# Filter.net
KiCad netlist of a schematic drawn in Altium Designer
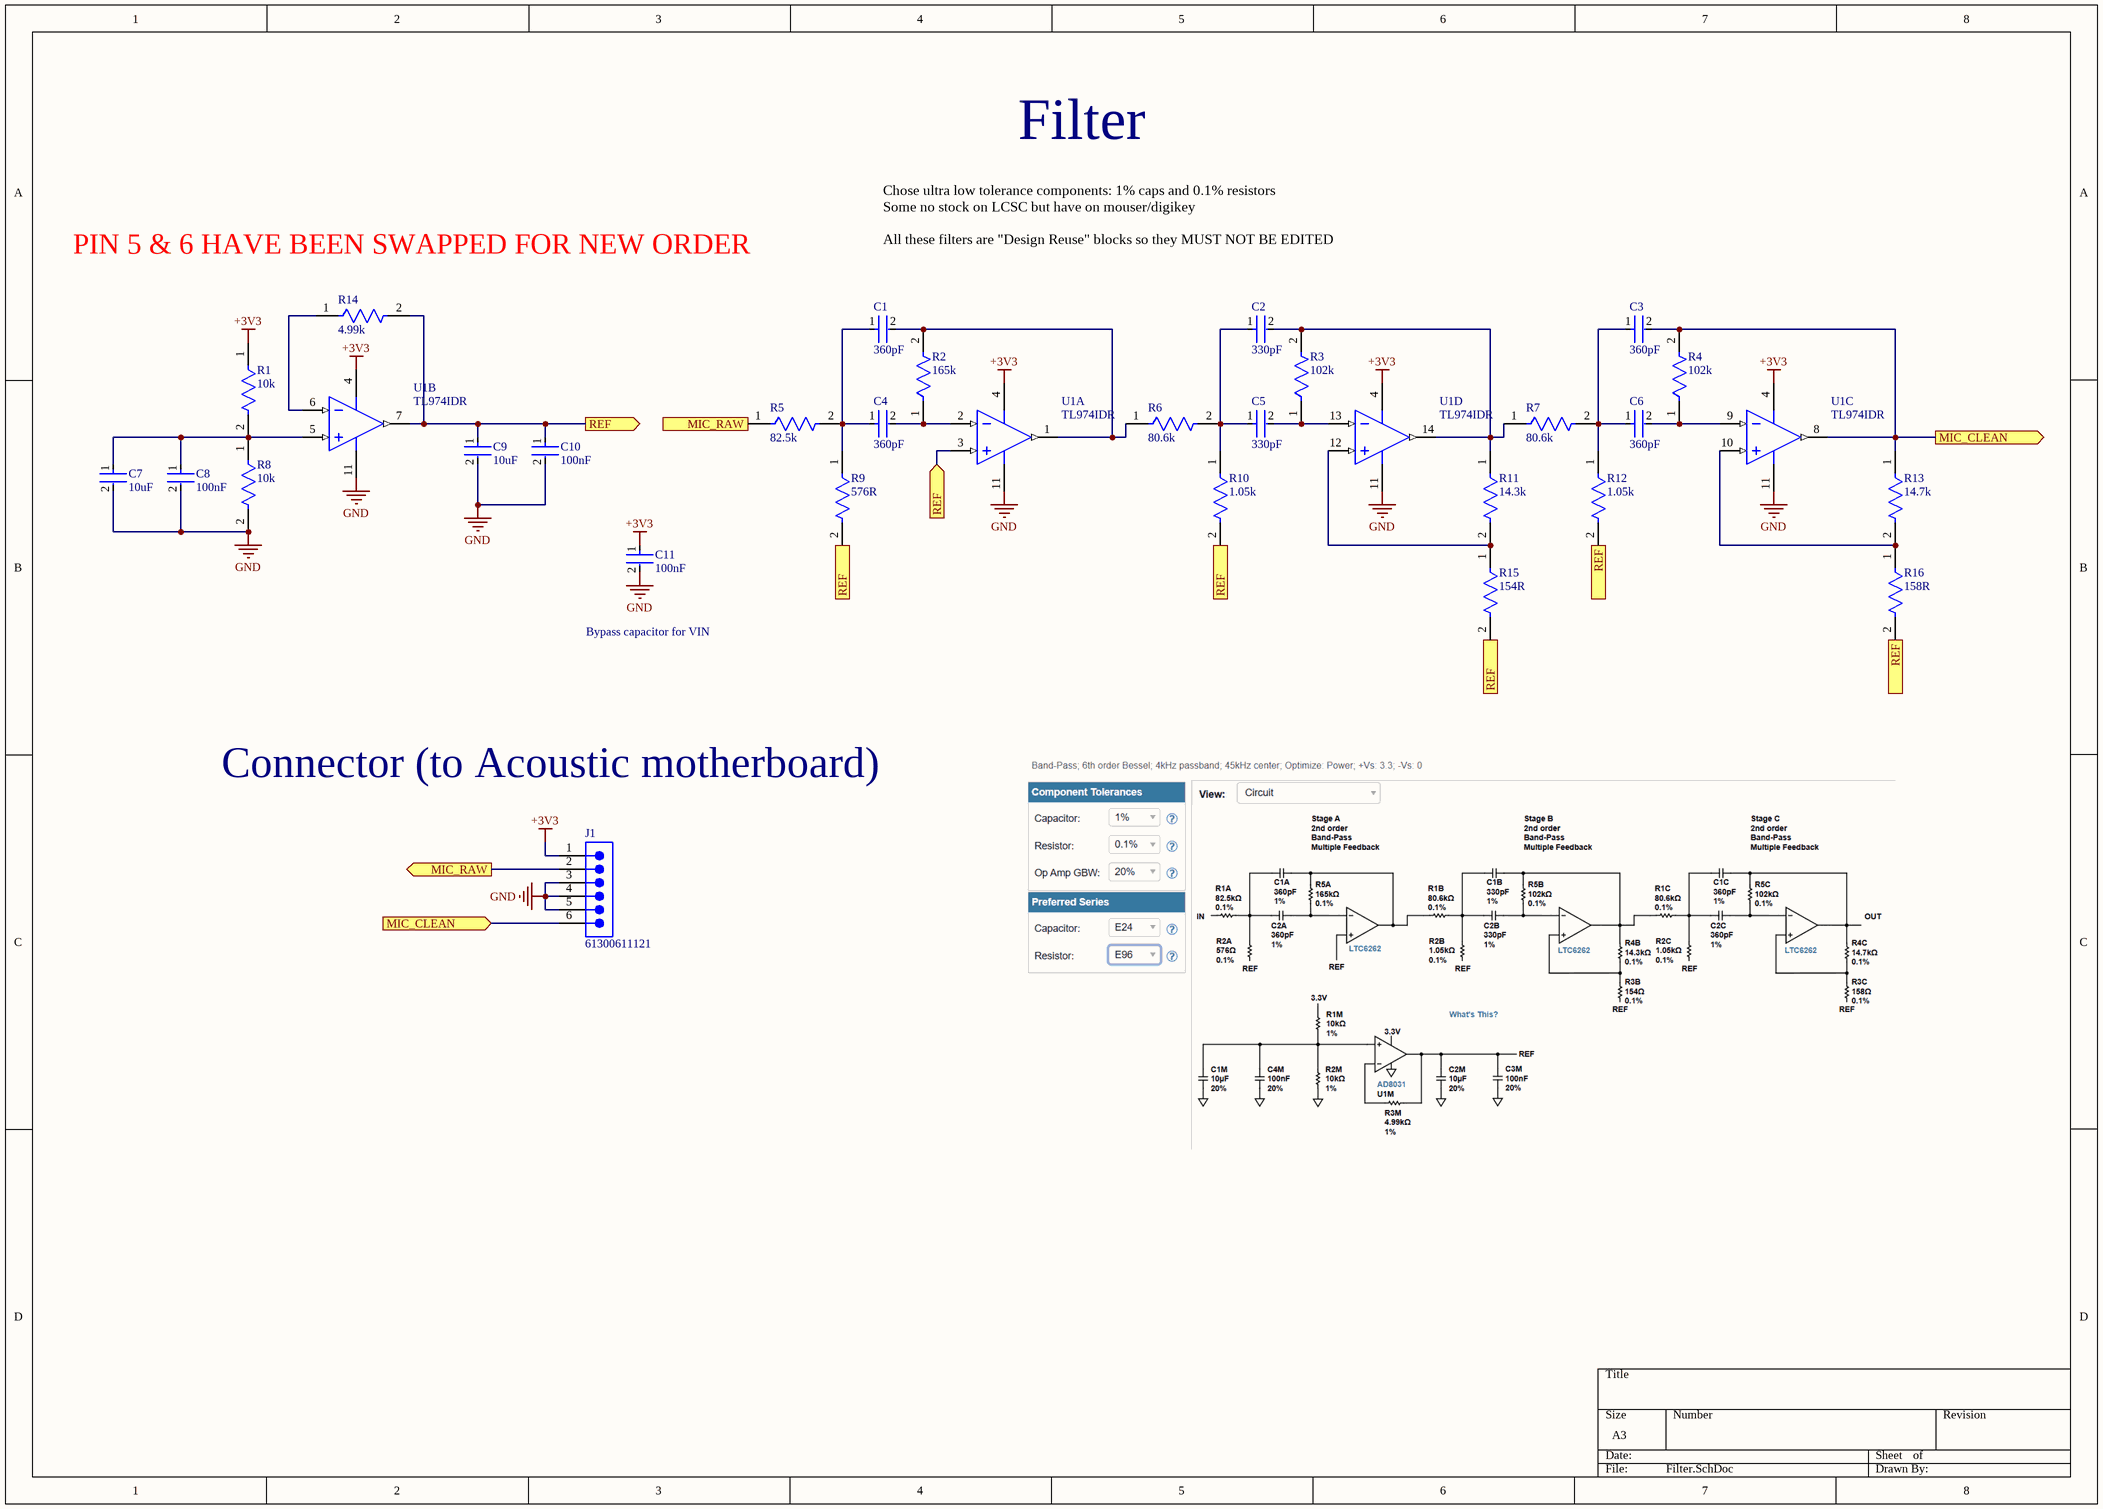
[diagram p0: Filter.SchDoc]

(export (version "E")
  (design (tool "Eeschema 10.0.6"))
  (components
    (comp (ref "C1")
      (value "360pF")
      (footprint "FP-GCM188-0_1-IPC_B")
      (libsource (lib "Hornet X Elec") (part "02cd4be3c70576c341d710602a673aa"))
    )
    (comp (ref "C2")
      (value "330pF")
      (footprint "FP-GCM188-0_1-IPC_B")
      (libsource (lib "Hornet X Elec") (part "02cd4be3c70576c341d710602a673aa"))
    )
    (comp (ref "C3")
      (value "360pF")
      (footprint "FP-GCM188-0_1-IPC_B")
      (libsource (lib "Hornet X Elec") (part "02cd4be3c70576c341d710602a673aa"))
    )
    (comp (ref "C4")
      (value "360pF")
      (footprint "FP-GCM188-0_1-IPC_B")
      (libsource (lib "Hornet X Elec") (part "02cd4be3c70576c341d710602a673aa"))
    )
    (comp (ref "C5")
      (value "330pF")
      (footprint "FP-GCM188-0_1-IPC_B")
      (libsource (lib "Hornet X Elec") (part "02cd4be3c70576c341d710602a673aa"))
    )
    (comp (ref "C6")
      (value "360pF")
      (footprint "FP-GCM188-0_1-IPC_B")
      (libsource (lib "Hornet X Elec") (part "02cd4be3c70576c341d710602a673aa"))
    )
    (comp (ref "C7")
      (value "10uF")
      (footprint "FP-GCM188-0_1-IPC_B")
      (libsource (lib "Hornet X Elec") (part "02cd4be3c70576c341d710602a673aa"))
    )
    (comp (ref "C8")
      (value "100nF")
      (footprint "FP-GCM188-0_1-IPC_B")
      (libsource (lib "Hornet X Elec") (part "02cd4be3c70576c341d710602a673aa"))
    )
    (comp (ref "C9")
      (value "10uF")
      (footprint "FP-GCM188-0_1-IPC_B")
      (libsource (lib "Hornet X Elec") (part "02cd4be3c70576c341d710602a673aa"))
    )
    (comp (ref "C10")
      (value "100nF")
      (footprint "FP-GCM188-0_1-IPC_B")
      (libsource (lib "Hornet X Elec") (part "02cd4be3c70576c341d710602a673aa"))
    )
    (comp (ref "C11")
      (value "100nF")
      (footprint "FP-GCM188-0_1-IPC_B")
      (libsource (lib "Hornet X Elec") (part "02cd4be3c70576c341d710602a673aa"))
    )
    (comp (ref "J1")
      (value "61300611121")
      (footprint "61300611121-Footprint-1")
      (description "6P Single Row 2.54mm Wurth Elektronik Header Pin (inverted 3D model)")
      (libsource (lib "Hornet X Elec") (part "Header_Male_1R_06P"))
    )
    (comp (ref "R1")
      (value "10k")
      (footprint "FP-RT0603-IPC_B")
      (fields (field (name "POWER") "100mW") (field (name "TOLERANCE") "1%"))
      (libsource (lib "Hornet X Elec") (part "1029c3af85768c4190bb7ad29bc67b5"))
    )
    (comp (ref "R2")
      (value "165k")
      (footprint "FP-RT0603-IPC_B")
      (description "165k Fixed Resistor, Thin Film, 0.1W, 165000ohm, 75V, 0.1% +/-Tol, 25ppm/Cel, Surface Mount, 0603")
      (fields (field (name "POWER") "100mW") (field (name "TOLERANCE") "0.1%"))
      (libsource (lib "Hornet X Elec") (part "1029c3af85768c4190bb7ad29bc67b5"))
    )
    (comp (ref "R3")
      (value "102k")
      (footprint "FP-RT0603-IPC_B")
      (description "102k Fixed Resistor, Thin Film, 0.1W, 102000ohm, 75V, 0.1% +/-Tol, 25ppm/Cel, Surface Mount, 0603")
      (fields (field (name "POWER") "100mW") (field (name "TOLERANCE") "0.1%"))
      (libsource (lib "Hornet X Elec") (part "1029c3af85768c4190bb7ad29bc67b5"))
    )
    (comp (ref "R4")
      (value "102k")
      (footprint "FP-RT0603-IPC_B")
      (description "102k Fixed Resistor, Thin Film, 0.1W, 102000ohm, 75V, 0.1% +/-Tol, 25ppm/Cel, Surface Mount, 0603")
      (fields (field (name "POWER") "100mW") (field (name "TOLERANCE") "0.1%"))
      (libsource (lib "Hornet X Elec") (part "1029c3af85768c4190bb7ad29bc67b5"))
    )
    (comp (ref "R5")
      (value "82.5k")
      (footprint "FP-RT0603-IPC_B")
      (description "82.5k Fixed Resistor, Thin Film, 0.1W, 82500ohm, 75V, 0.1% +/-Tol, 25ppm/Cel, Surface Mount, 0603")
      (fields (field (name "TOLERANCE") "0.1%") (field (name "POWER") "100mW"))
      (libsource (lib "Hornet X Elec") (part "1029c3af85768c4190bb7ad29bc67b5"))
    )
    (comp (ref "R6")
      (value "80.6k")
      (footprint "FP-RT0603-IPC_B")
      (description "80.6k Fixed Resistor, Thin Film, 0.1W, 80600ohm, 75V, 0.1% +/-Tol, 25ppm/Cel, Surface Mount, 0603")
      (fields (field (name "TOLERANCE") "0.1%") (field (name "POWER") "100mW"))
      (libsource (lib "Hornet X Elec") (part "1029c3af85768c4190bb7ad29bc67b5"))
    )
    (comp (ref "R7")
      (value "80.6k")
      (footprint "FP-RT0603-IPC_B")
      (description "80.6k Fixed Resistor, Thin Film, 0.1W, 80600ohm, 75V, 0.1% +/-Tol, 25ppm/Cel, Surface Mount, 0603")
      (fields (field (name "TOLERANCE") "0.1%") (field (name "POWER") "100mW"))
      (libsource (lib "Hornet X Elec") (part "1029c3af85768c4190bb7ad29bc67b5"))
    )
    (comp (ref "R8")
      (value "10k")
      (footprint "FP-RT0603-IPC_B")
      (fields (field (name "POWER") "100mW") (field (name "TOLERANCE") "1%"))
      (libsource (lib "Hornet X Elec") (part "1029c3af85768c4190bb7ad29bc67b5"))
    )
    (comp (ref "R9")
      (value "576R")
      (footprint "FP-RT0603-IPC_B")
      (description "576R Fixed Resistor, Thin Film, 0.1W, 576ohm, 75V, 0.1% +/-Tol, 25ppm/Cel, Surface Mount, 0603")
      (fields (field (name "POWER") "100mW") (field (name "TOLERANCE") "0.1%"))
      (libsource (lib "Hornet X Elec") (part "1029c3af85768c4190bb7ad29bc67b5"))
    )
    (comp (ref "R10")
      (value "1.05k")
      (footprint "FP-RT0603-IPC_B")
      (description "1.05k Fixed Resistor, Thin Film, 0.1W, 1050ohm, 75V, 0.1% +/-Tol, 25ppm/Cel, Surface Mount, 0603")
      (fields (field (name "TOLERANCE") "0.1%") (field (name "POWER") "100mW"))
      (libsource (lib "Hornet X Elec") (part "1029c3af85768c4190bb7ad29bc67b5"))
    )
    (comp (ref "R11")
      (value "14.3k")
      (footprint "FP-RT0603-IPC_B")
      (description "14.3k Fixed Resistor, Thin Film, 0.1W, 14300ohm, 75V, 0.1% +/-Tol, 25ppm/Cel, Surface Mount, 0603")
      (fields (field (name "TOLERANCE") "0.1%") (field (name "POWER") "100mW"))
      (libsource (lib "Hornet X Elec") (part "1029c3af85768c4190bb7ad29bc67b5"))
    )
    (comp (ref "R12")
      (value "1.05k")
      (footprint "FP-RT0603-IPC_B")
      (description "1.05k Fixed Resistor, Thin Film, 0.1W, 1050ohm, 75V, 0.1% +/-Tol, 25ppm/Cel, Surface Mount, 0603")
      (fields (field (name "TOLERANCE") "0.1%") (field (name "POWER") "100mW"))
      (libsource (lib "Hornet X Elec") (part "1029c3af85768c4190bb7ad29bc67b5"))
    )
    (comp (ref "R13")
      (value "14.7k")
      (footprint "FP-RT0603-IPC_B")
      (description "14.7k Fixed Resistor, Thin Film, 0.1W, 14700ohm, 75V, 0.1% +/-Tol, 25ppm/Cel, Surface Mount, 0603")
      (fields (field (name "TOLERANCE") "0.1%") (field (name "POWER") "100mW"))
      (libsource (lib "Hornet X Elec") (part "1029c3af85768c4190bb7ad29bc67b5"))
    )
    (comp (ref "R14")
      (value "4.99k")
      (footprint "FP-RT0603-IPC_B")
      (fields (field (name "TOLERANCE") "1%") (field (name "POWER") "100mW"))
      (libsource (lib "Hornet X Elec") (part "1029c3af85768c4190bb7ad29bc67b5"))
    )
    (comp (ref "R15")
      (value "154R")
      (footprint "FP-RT0603-IPC_B")
      (description "154R Fixed Resistor, Thin Film, 0.1W, 154ohm, 75V, 0.1% +/-Tol, 25ppm/Cel, Surface Mount, 0603")
      (fields (field (name "POWER") "100mW") (field (name "TOLERANCE") "0.1%"))
      (libsource (lib "Hornet X Elec") (part "1029c3af85768c4190bb7ad29bc67b5"))
    )
    (comp (ref "R16")
      (value "158R")
      (footprint "FP-RT0603-IPC_B")
      (description "158R Fixed Resistor, Thin Film, 0.1W, 158ohm, 75V, 0.1% +/-Tol, 25ppm/Cel, Surface Mount, 0603")
      (fields (field (name "POWER") "100mW") (field (name "TOLERANCE") "0.1%"))
      (libsource (lib "Hornet X Elec") (part "1029c3af85768c4190bb7ad29bc67b5"))
    )
    (comp (ref "U1")
      (value "TL974IDR")
      (footprint "D0014A_N")
      (description "Operational Amplifier, 4 Func, 6000uV Offset-Max, BIPolar, PDSO14")
      (libsource (lib "Hornet X Elec") (part "TI-TLXX4X_MC3403-X14"))
    )
  )
  (nets
    (net (code "1") (name "+3V3") (class "Default")
      (node (ref "C11") (pin "1") (pinfunction "1_1") (pintype "passive"))
      (node (ref "J1") (pin "1") (pinfunction "1_1") (pintype "passive"))
      (node (ref "R1") (pin "1") (pinfunction "1_1") (pintype "passive"))
      (node (ref "U1") (pin "4") (pinfunction "VCC+_4") (pintype "power_in"))
    )
    (net (code "2") (name "/MIC_CLEAN") (class "Default")
      (node (ref "C3") (pin "2") (pinfunction "2_2") (pintype "passive"))
      (node (ref "J1") (pin "6") (pinfunction "6_6") (pintype "passive"))
      (node (ref "R13") (pin "1") (pinfunction "1_1") (pintype "passive"))
      (node (ref "R4") (pin "2") (pinfunction "2_2") (pintype "passive"))
      (node (ref "U1") (pin "8") (pinfunction "OUT3_8") (pintype "output"))
    )
    (net (code "3") (name "/MIC_RAW") (class "Default")
      (node (ref "J1") (pin "2") (pinfunction "2_2") (pintype "passive"))
      (node (ref "R5") (pin "1") (pinfunction "1_1") (pintype "passive"))
    )
    (net (code "4") (name "/REF") (class "Default")
      (node (ref "C10") (pin "1") (pinfunction "1_1") (pintype "passive"))
      (node (ref "C9") (pin "1") (pinfunction "1_1") (pintype "passive"))
      (node (ref "R10") (pin "2") (pinfunction "2_2") (pintype "passive"))
      (node (ref "R12") (pin "2") (pinfunction "2_2") (pintype "passive"))
      (node (ref "R14") (pin "2") (pinfunction "2_2") (pintype "passive"))
      (node (ref "R15") (pin "2") (pinfunction "2_2") (pintype "passive"))
      (node (ref "R16") (pin "2") (pinfunction "2_2") (pintype "passive"))
      (node (ref "R9") (pin "2") (pinfunction "2_2") (pintype "passive"))
      (node (ref "U1") (pin "3") (pinfunction "IN1+_3") (pintype "input"))
      (node (ref "U1") (pin "7") (pinfunction "OUT2_7") (pintype "output"))
    )
    (net (code "5") (name "GND") (class "Default")
      (node (ref "C10") (pin "2") (pinfunction "2_2") (pintype "passive"))
      (node (ref "C11") (pin "2") (pinfunction "2_2") (pintype "passive"))
      (node (ref "C7") (pin "2") (pinfunction "2_2") (pintype "passive"))
      (node (ref "C8") (pin "2") (pinfunction "2_2") (pintype "passive"))
      (node (ref "C9") (pin "2") (pinfunction "2_2") (pintype "passive"))
      (node (ref "J1") (pin "3") (pinfunction "3_3") (pintype "passive"))
      (node (ref "J1") (pin "4") (pinfunction "4_4") (pintype "passive"))
      (node (ref "J1") (pin "5") (pinfunction "5_5") (pintype "passive"))
      (node (ref "R8") (pin "2") (pinfunction "2_2") (pintype "passive"))
      (node (ref "U1") (pin "11") (pinfunction "VCC-_11") (pintype "power_in"))
    )
    (net (code "6") (name "Net-(C1-Pad1)") (class "Default")
      (node (ref "C1") (pin "1") (pinfunction "1_1") (pintype "passive"))
      (node (ref "C4") (pin "1") (pinfunction "1_1") (pintype "passive"))
      (node (ref "R5") (pin "2") (pinfunction "2_2") (pintype "passive"))
      (node (ref "R9") (pin "1") (pinfunction "1_1") (pintype "passive"))
    )
    (net (code "7") (name "Net-(C2-Pad1)") (class "Default")
      (node (ref "C2") (pin "1") (pinfunction "1_1") (pintype "passive"))
      (node (ref "C5") (pin "1") (pinfunction "1_1") (pintype "passive"))
      (node (ref "R10") (pin "1") (pinfunction "1_1") (pintype "passive"))
      (node (ref "R6") (pin "2") (pinfunction "2_2") (pintype "passive"))
    )
    (net (code "8") (name "Net-(C3-Pad1)") (class "Default")
      (node (ref "C3") (pin "1") (pinfunction "1_1") (pintype "passive"))
      (node (ref "C6") (pin "1") (pinfunction "1_1") (pintype "passive"))
      (node (ref "R12") (pin "1") (pinfunction "1_1") (pintype "passive"))
      (node (ref "R7") (pin "2") (pinfunction "2_2") (pintype "passive"))
    )
    (net (code "9") (name "Net-(U1A-IN1-)") (class "Default")
      (node (ref "C4") (pin "2") (pinfunction "2_2") (pintype "passive"))
      (node (ref "R2") (pin "1") (pinfunction "1_1") (pintype "passive"))
      (node (ref "U1") (pin "2") (pinfunction "IN1-_2") (pintype "input"))
    )
    (net (code "10") (name "Net-(U1A-OUT1)") (class "Default")
      (node (ref "C1") (pin "2") (pinfunction "2_2") (pintype "passive"))
      (node (ref "R2") (pin "2") (pinfunction "2_2") (pintype "passive"))
      (node (ref "R6") (pin "1") (pinfunction "1_1") (pintype "passive"))
      (node (ref "U1") (pin "1") (pinfunction "OUT1_1") (pintype "output"))
    )
    (net (code "11") (name "Net-(U1B-IN2+)") (class "Default")
      (node (ref "C7") (pin "1") (pinfunction "1_1") (pintype "passive"))
      (node (ref "C8") (pin "1") (pinfunction "1_1") (pintype "passive"))
      (node (ref "R1") (pin "2") (pinfunction "2_2") (pintype "passive"))
      (node (ref "R8") (pin "1") (pinfunction "1_1") (pintype "passive"))
      (node (ref "U1") (pin "5") (pinfunction "IN2+_5") (pintype "input"))
    )
    (net (code "12") (name "Net-(U1B-IN2-)") (class "Default")
      (node (ref "R14") (pin "1") (pinfunction "1_1") (pintype "passive"))
      (node (ref "U1") (pin "6") (pinfunction "IN2-_6") (pintype "input"))
    )
    (net (code "13") (name "Net-(U1C-IN3+)") (class "Default")
      (node (ref "R13") (pin "2") (pinfunction "2_2") (pintype "passive"))
      (node (ref "R16") (pin "1") (pinfunction "1_1") (pintype "passive"))
      (node (ref "U1") (pin "10") (pinfunction "IN3+_10") (pintype "input"))
    )
    (net (code "14") (name "Net-(U1C-IN3-)") (class "Default")
      (node (ref "C6") (pin "2") (pinfunction "2_2") (pintype "passive"))
      (node (ref "R4") (pin "1") (pinfunction "1_1") (pintype "passive"))
      (node (ref "U1") (pin "9") (pinfunction "IN3-_9") (pintype "input"))
    )
    (net (code "15") (name "Net-(U1D-IN4+)") (class "Default")
      (node (ref "R11") (pin "2") (pinfunction "2_2") (pintype "passive"))
      (node (ref "R15") (pin "1") (pinfunction "1_1") (pintype "passive"))
      (node (ref "U1") (pin "12") (pinfunction "IN4+_12") (pintype "input"))
    )
    (net (code "16") (name "Net-(U1D-IN4-)") (class "Default")
      (node (ref "C5") (pin "2") (pinfunction "2_2") (pintype "passive"))
      (node (ref "R3") (pin "1") (pinfunction "1_1") (pintype "passive"))
      (node (ref "U1") (pin "13") (pinfunction "IN4-_13") (pintype "input"))
    )
    (net (code "17") (name "Net-(U1D-OUT4)") (class "Default")
      (node (ref "C2") (pin "2") (pinfunction "2_2") (pintype "passive"))
      (node (ref "R11") (pin "1") (pinfunction "1_1") (pintype "passive"))
      (node (ref "R3") (pin "2") (pinfunction "2_2") (pintype "passive"))
      (node (ref "R7") (pin "1") (pinfunction "1_1") (pintype "passive"))
      (node (ref "U1") (pin "14") (pinfunction "OUT4_14") (pintype "output"))
    )
  )
)
